# MIDI_Input.net
KiCad netlist of a schematic drawn in EAGLE
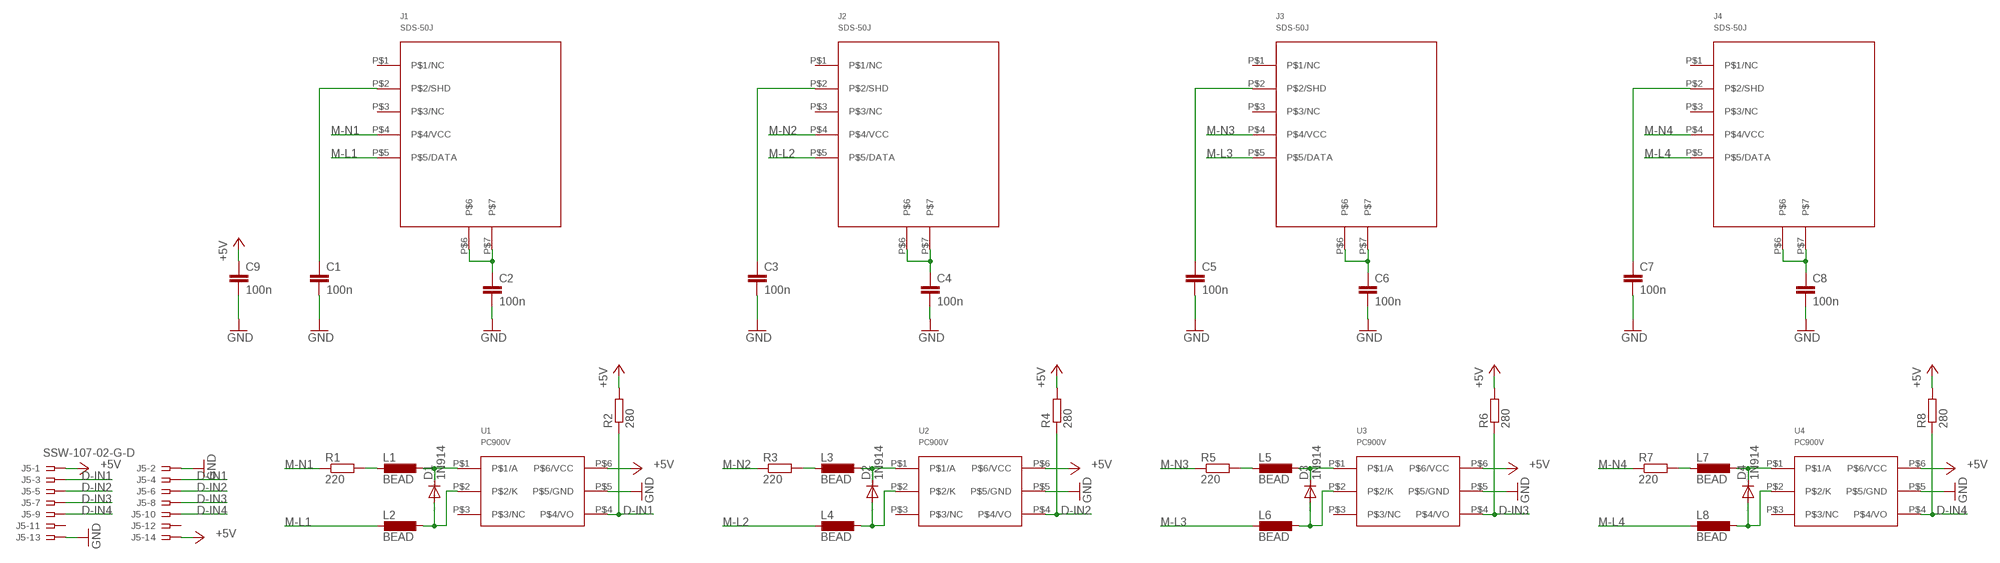
[diagram p0: schematic, sheet 1]

(export (version "E")
  (design (tool "Eeschema 10.0.6"))
  (components
    (comp (ref "C1")
      (value "100n")
      (footprint "eagle-import:C0805")
      (libsource (lib "eagle-import") (part "C-EUC0805"))
    )
    (comp (ref "C2")
      (value "100n")
      (footprint "eagle-import:C0805")
      (libsource (lib "eagle-import") (part "C-EUC0805"))
    )
    (comp (ref "C3")
      (value "100n")
      (footprint "eagle-import:C0805")
      (libsource (lib "eagle-import") (part "C-EUC0805"))
    )
    (comp (ref "C4")
      (value "100n")
      (footprint "eagle-import:C0805")
      (libsource (lib "eagle-import") (part "C-EUC0805"))
    )
    (comp (ref "C5")
      (value "100n")
      (footprint "eagle-import:C0805")
      (libsource (lib "eagle-import") (part "C-EUC0805"))
    )
    (comp (ref "C6")
      (value "100n")
      (footprint "eagle-import:C0805")
      (libsource (lib "eagle-import") (part "C-EUC0805"))
    )
    (comp (ref "C7")
      (value "100n")
      (footprint "eagle-import:C0805")
      (libsource (lib "eagle-import") (part "C-EUC0805"))
    )
    (comp (ref "C8")
      (value "100n")
      (footprint "eagle-import:C0805")
      (libsource (lib "eagle-import") (part "C-EUC0805"))
    )
    (comp (ref "C9")
      (value "100n")
      (footprint "eagle-import:C0805")
      (libsource (lib "eagle-import") (part "C-EUC0805"))
    )
    (comp (ref "D1")
      (value "1N914")
      (footprint "eagle-import:SOD323-W")
      (libsource (lib "eagle-import") (part "1N914"))
    )
    (comp (ref "D2")
      (value "1N914")
      (footprint "eagle-import:SOD323-W")
      (libsource (lib "eagle-import") (part "1N914"))
    )
    (comp (ref "D3")
      (value "1N914")
      (footprint "eagle-import:SOD323-W")
      (libsource (lib "eagle-import") (part "1N914"))
    )
    (comp (ref "D4")
      (value "1N914")
      (footprint "eagle-import:SOD323-W")
      (libsource (lib "eagle-import") (part "1N914"))
    )
    (comp (ref "J1")
      (value "SDS-50J")
      (footprint "eagle-import:SDS-50J")
      (libsource (lib "eagle-import") (part "SDS-50J"))
    )
    (comp (ref "J2")
      (value "SDS-50J")
      (footprint "eagle-import:SDS-50J")
      (libsource (lib "eagle-import") (part "SDS-50J"))
    )
    (comp (ref "J3")
      (value "SDS-50J")
      (footprint "eagle-import:SDS-50J")
      (libsource (lib "eagle-import") (part "SDS-50J"))
    )
    (comp (ref "J4")
      (value "SDS-50J")
      (footprint "eagle-import:SDS-50J")
      (libsource (lib "eagle-import") (part "SDS-50J"))
    )
    (comp (ref "J5")
      (value "SSW-107-02-G-D")
      (footprint "eagle-import:SSW-107-02-G-D")
      (fields (field (name "MF") "Samtec Inc."))
      (libsource (lib "eagle-import") (part "SSW-107-02-G-D"))
    )
    (comp (ref "L1")
      (value "BEAD")
      (footprint "eagle-import:L0805")
      (libsource (lib "eagle-import") (part "BEAD"))
    )
    (comp (ref "L2")
      (value "BEAD")
      (footprint "eagle-import:L0805")
      (libsource (lib "eagle-import") (part "BEAD"))
    )
    (comp (ref "L3")
      (value "BEAD")
      (footprint "eagle-import:L0805")
      (libsource (lib "eagle-import") (part "BEAD"))
    )
    (comp (ref "L4")
      (value "BEAD")
      (footprint "eagle-import:L0805")
      (libsource (lib "eagle-import") (part "BEAD"))
    )
    (comp (ref "L5")
      (value "BEAD")
      (footprint "eagle-import:L0805")
      (libsource (lib "eagle-import") (part "BEAD"))
    )
    (comp (ref "L6")
      (value "BEAD")
      (footprint "eagle-import:L0805")
      (libsource (lib "eagle-import") (part "BEAD"))
    )
    (comp (ref "L7")
      (value "BEAD")
      (footprint "eagle-import:L0805")
      (libsource (lib "eagle-import") (part "BEAD"))
    )
    (comp (ref "L8")
      (value "BEAD")
      (footprint "eagle-import:L0805")
      (libsource (lib "eagle-import") (part "BEAD"))
    )
    (comp (ref "R1")
      (value "220")
      (footprint "eagle-import:R0805")
      (libsource (lib "eagle-import") (part "R-EU_R0805"))
    )
    (comp (ref "R2")
      (value "280")
      (footprint "eagle-import:R0805")
      (libsource (lib "eagle-import") (part "R-EU_R0805"))
    )
    (comp (ref "R3")
      (value "220")
      (footprint "eagle-import:R0805")
      (libsource (lib "eagle-import") (part "R-EU_R0805"))
    )
    (comp (ref "R4")
      (value "280")
      (footprint "eagle-import:R0805")
      (libsource (lib "eagle-import") (part "R-EU_R0805"))
    )
    (comp (ref "R5")
      (value "220")
      (footprint "eagle-import:R0805")
      (libsource (lib "eagle-import") (part "R-EU_R0805"))
    )
    (comp (ref "R6")
      (value "280")
      (footprint "eagle-import:R0805")
      (libsource (lib "eagle-import") (part "R-EU_R0805"))
    )
    (comp (ref "R7")
      (value "220")
      (footprint "eagle-import:R0805")
      (libsource (lib "eagle-import") (part "R-EU_R0805"))
    )
    (comp (ref "R8")
      (value "280")
      (footprint "eagle-import:R0805")
      (libsource (lib "eagle-import") (part "R-EU_R0805"))
    )
    (comp (ref "U1")
      (value "PC900V")
      (footprint "eagle-import:DIL06")
      (libsource (lib "eagle-import") (part "PC900V"))
    )
    (comp (ref "U2")
      (value "PC900V")
      (footprint "eagle-import:DIL06")
      (libsource (lib "eagle-import") (part "PC900V"))
    )
    (comp (ref "U3")
      (value "PC900V")
      (footprint "eagle-import:DIL06")
      (libsource (lib "eagle-import") (part "PC900V"))
    )
    (comp (ref "U4")
      (value "PC900V")
      (footprint "eagle-import:DIL06")
      (libsource (lib "eagle-import") (part "PC900V"))
    )
  )
  (nets
    (net (code "1") (name "+5V") (class "Default")
      (node (ref "C9") (pin "1") (pinfunction "1_1") (pintype "passive"))
      (node (ref "J5") (pin "1") (pinfunction "1_1") (pintype "passive"))
      (node (ref "J5") (pin "14") (pinfunction "1_14") (pintype "passive"))
      (node (ref "R2") (pin "2") (pinfunction "2_2") (pintype "passive"))
      (node (ref "R4") (pin "2") (pinfunction "2_2") (pintype "passive"))
      (node (ref "R6") (pin "2") (pinfunction "2_2") (pintype "passive"))
      (node (ref "R8") (pin "2") (pinfunction "2_2") (pintype "passive"))
      (node (ref "U1") (pin "P$6") (pinfunction "P$6/VCC_P$6") (pintype "bidirectional"))
      (node (ref "U2") (pin "P$6") (pinfunction "P$6/VCC_P$6") (pintype "bidirectional"))
      (node (ref "U3") (pin "P$6") (pinfunction "P$6/VCC_P$6") (pintype "bidirectional"))
      (node (ref "U4") (pin "P$6") (pinfunction "P$6/VCC_P$6") (pintype "bidirectional"))
    )
    (net (code "2") (name "/D-IN1") (class "Default")
      (node (ref "J5") (pin "3") (pinfunction "1_3") (pintype "passive"))
      (node (ref "J5") (pin "4") (pinfunction "1_4") (pintype "passive"))
      (node (ref "R2") (pin "1") (pinfunction "1_1") (pintype "passive"))
      (node (ref "U1") (pin "P$4") (pinfunction "P$4/VO_P$4") (pintype "bidirectional"))
    )
    (net (code "3") (name "/D-IN2") (class "Default")
      (node (ref "J5") (pin "5") (pinfunction "1_5") (pintype "passive"))
      (node (ref "J5") (pin "6") (pinfunction "1_6") (pintype "passive"))
      (node (ref "R4") (pin "1") (pinfunction "1_1") (pintype "passive"))
      (node (ref "U2") (pin "P$4") (pinfunction "P$4/VO_P$4") (pintype "bidirectional"))
    )
    (net (code "4") (name "/D-IN3") (class "Default")
      (node (ref "J5") (pin "7") (pinfunction "1_7") (pintype "passive"))
      (node (ref "J5") (pin "8") (pinfunction "1_8") (pintype "passive"))
      (node (ref "R6") (pin "1") (pinfunction "1_1") (pintype "passive"))
      (node (ref "U3") (pin "P$4") (pinfunction "P$4/VO_P$4") (pintype "bidirectional"))
    )
    (net (code "5") (name "/D-IN4") (class "Default")
      (node (ref "J5") (pin "10") (pinfunction "1_10") (pintype "passive"))
      (node (ref "J5") (pin "9") (pinfunction "1_9") (pintype "passive"))
      (node (ref "R8") (pin "1") (pinfunction "1_1") (pintype "passive"))
      (node (ref "U4") (pin "P$4") (pinfunction "P$4/VO_P$4") (pintype "bidirectional"))
    )
    (net (code "6") (name "/M-L1") (class "Default")
      (node (ref "J1") (pin "P$5") (pinfunction "P$5/DATA_P$5") (pintype "bidirectional"))
      (node (ref "L2") (pin "1") (pinfunction "1_1") (pintype "passive"))
    )
    (net (code "7") (name "/M-L2") (class "Default")
      (node (ref "J2") (pin "P$5") (pinfunction "P$5/DATA_P$5") (pintype "bidirectional"))
      (node (ref "L4") (pin "1") (pinfunction "1_1") (pintype "passive"))
    )
    (net (code "8") (name "/M-L3") (class "Default")
      (node (ref "J3") (pin "P$5") (pinfunction "P$5/DATA_P$5") (pintype "bidirectional"))
      (node (ref "L6") (pin "1") (pinfunction "1_1") (pintype "passive"))
    )
    (net (code "9") (name "/M-L4") (class "Default")
      (node (ref "J4") (pin "P$5") (pinfunction "P$5/DATA_P$5") (pintype "bidirectional"))
      (node (ref "L8") (pin "1") (pinfunction "1_1") (pintype "passive"))
    )
    (net (code "10") (name "/M-N1") (class "Default")
      (node (ref "J1") (pin "P$4") (pinfunction "P$4/VCC_P$4") (pintype "bidirectional"))
      (node (ref "R1") (pin "1") (pinfunction "1_1") (pintype "passive"))
    )
    (net (code "11") (name "/M-N2") (class "Default")
      (node (ref "J2") (pin "P$4") (pinfunction "P$4/VCC_P$4") (pintype "bidirectional"))
      (node (ref "R3") (pin "1") (pinfunction "1_1") (pintype "passive"))
    )
    (net (code "12") (name "/M-N3") (class "Default")
      (node (ref "J3") (pin "P$4") (pinfunction "P$4/VCC_P$4") (pintype "bidirectional"))
      (node (ref "R5") (pin "1") (pinfunction "1_1") (pintype "passive"))
    )
    (net (code "13") (name "/M-N4") (class "Default")
      (node (ref "J4") (pin "P$4") (pinfunction "P$4/VCC_P$4") (pintype "bidirectional"))
      (node (ref "R7") (pin "1") (pinfunction "1_1") (pintype "passive"))
    )
    (net (code "14") (name "GND") (class "Default")
      (node (ref "C1") (pin "2") (pinfunction "2_2") (pintype "passive"))
      (node (ref "C2") (pin "2") (pinfunction "2_2") (pintype "passive"))
      (node (ref "C3") (pin "2") (pinfunction "2_2") (pintype "passive"))
      (node (ref "C4") (pin "2") (pinfunction "2_2") (pintype "passive"))
      (node (ref "C5") (pin "2") (pinfunction "2_2") (pintype "passive"))
      (node (ref "C6") (pin "2") (pinfunction "2_2") (pintype "passive"))
      (node (ref "C7") (pin "2") (pinfunction "2_2") (pintype "passive"))
      (node (ref "C8") (pin "2") (pinfunction "2_2") (pintype "passive"))
      (node (ref "C9") (pin "2") (pinfunction "2_2") (pintype "passive"))
      (node (ref "J5") (pin "13") (pinfunction "1_13") (pintype "passive"))
      (node (ref "J5") (pin "2") (pinfunction "1_2") (pintype "passive"))
      (node (ref "U1") (pin "P$5") (pinfunction "P$5/GND_P$5") (pintype "bidirectional"))
      (node (ref "U2") (pin "P$5") (pinfunction "P$5/GND_P$5") (pintype "bidirectional"))
      (node (ref "U3") (pin "P$5") (pinfunction "P$5/GND_P$5") (pintype "bidirectional"))
      (node (ref "U4") (pin "P$5") (pinfunction "P$5/GND_P$5") (pintype "bidirectional"))
    )
    (net (code "15") (name "Net-(C2-Pad1)") (class "Default")
      (node (ref "C2") (pin "1") (pinfunction "1_1") (pintype "passive"))
      (node (ref "J1") (pin "P$6") (pinfunction "P$6_P$6") (pintype "bidirectional"))
      (node (ref "J1") (pin "P$7") (pinfunction "P$7_P$7") (pintype "bidirectional"))
    )
    (net (code "16") (name "Net-(C4-Pad1)") (class "Default")
      (node (ref "C4") (pin "1") (pinfunction "1_1") (pintype "passive"))
      (node (ref "J2") (pin "P$6") (pinfunction "P$6_P$6") (pintype "bidirectional"))
      (node (ref "J2") (pin "P$7") (pinfunction "P$7_P$7") (pintype "bidirectional"))
    )
    (net (code "17") (name "Net-(C6-Pad1)") (class "Default")
      (node (ref "C6") (pin "1") (pinfunction "1_1") (pintype "passive"))
      (node (ref "J3") (pin "P$6") (pinfunction "P$6_P$6") (pintype "bidirectional"))
      (node (ref "J3") (pin "P$7") (pinfunction "P$7_P$7") (pintype "bidirectional"))
    )
    (net (code "18") (name "Net-(C8-Pad1)") (class "Default")
      (node (ref "C8") (pin "1") (pinfunction "1_1") (pintype "passive"))
      (node (ref "J4") (pin "P$6") (pinfunction "P$6_P$6") (pintype "bidirectional"))
      (node (ref "J4") (pin "P$7") (pinfunction "P$7_P$7") (pintype "bidirectional"))
    )
    (net (code "19") (name "Net-(J1-P$2{slash}SHD)") (class "Default")
      (node (ref "C1") (pin "1") (pinfunction "1_1") (pintype "passive"))
      (node (ref "J1") (pin "P$2") (pinfunction "P$2/SHD_P$2") (pintype "bidirectional"))
    )
    (net (code "20") (name "Net-(J2-P$2{slash}SHD)") (class "Default")
      (node (ref "C3") (pin "1") (pinfunction "1_1") (pintype "passive"))
      (node (ref "J2") (pin "P$2") (pinfunction "P$2/SHD_P$2") (pintype "bidirectional"))
    )
    (net (code "21") (name "Net-(J3-P$2{slash}SHD)") (class "Default")
      (node (ref "C5") (pin "1") (pinfunction "1_1") (pintype "passive"))
      (node (ref "J3") (pin "P$2") (pinfunction "P$2/SHD_P$2") (pintype "bidirectional"))
    )
    (net (code "22") (name "Net-(J4-P$2{slash}SHD)") (class "Default")
      (node (ref "C7") (pin "1") (pinfunction "1_1") (pintype "passive"))
      (node (ref "J4") (pin "P$2") (pinfunction "P$2/SHD_P$2") (pintype "bidirectional"))
    )
    (net (code "23") (name "Net-(L1-Pad1)") (class "Default")
      (node (ref "L1") (pin "1") (pinfunction "1_1") (pintype "passive"))
      (node (ref "R1") (pin "2") (pinfunction "2_2") (pintype "passive"))
    )
    (net (code "24") (name "Net-(L3-Pad1)") (class "Default")
      (node (ref "L3") (pin "1") (pinfunction "1_1") (pintype "passive"))
      (node (ref "R3") (pin "2") (pinfunction "2_2") (pintype "passive"))
    )
    (net (code "25") (name "Net-(L5-Pad1)") (class "Default")
      (node (ref "L5") (pin "1") (pinfunction "1_1") (pintype "passive"))
      (node (ref "R5") (pin "2") (pinfunction "2_2") (pintype "passive"))
    )
    (net (code "26") (name "Net-(L7-Pad1)") (class "Default")
      (node (ref "L7") (pin "1") (pinfunction "1_1") (pintype "passive"))
      (node (ref "R7") (pin "2") (pinfunction "2_2") (pintype "passive"))
    )
    (net (code "27") (name "Net-(U1-P$1{slash}A)") (class "Default")
      (node (ref "D1") (pin "C") (pinfunction "C_C") (pintype "passive"))
      (node (ref "L1") (pin "2") (pinfunction "2_2") (pintype "passive"))
      (node (ref "U1") (pin "P$1") (pinfunction "P$1/A_P$1") (pintype "bidirectional"))
    )
    (net (code "28") (name "Net-(U1-P$2{slash}K)") (class "Default")
      (node (ref "D1") (pin "A") (pinfunction "A_A") (pintype "passive"))
      (node (ref "L2") (pin "2") (pinfunction "2_2") (pintype "passive"))
      (node (ref "U1") (pin "P$2") (pinfunction "P$2/K_P$2") (pintype "bidirectional"))
    )
    (net (code "29") (name "Net-(U2-P$1{slash}A)") (class "Default")
      (node (ref "D2") (pin "C") (pinfunction "C_C") (pintype "passive"))
      (node (ref "L3") (pin "2") (pinfunction "2_2") (pintype "passive"))
      (node (ref "U2") (pin "P$1") (pinfunction "P$1/A_P$1") (pintype "bidirectional"))
    )
    (net (code "30") (name "Net-(U2-P$2{slash}K)") (class "Default")
      (node (ref "D2") (pin "A") (pinfunction "A_A") (pintype "passive"))
      (node (ref "L4") (pin "2") (pinfunction "2_2") (pintype "passive"))
      (node (ref "U2") (pin "P$2") (pinfunction "P$2/K_P$2") (pintype "bidirectional"))
    )
    (net (code "31") (name "Net-(U3-P$1{slash}A)") (class "Default")
      (node (ref "D3") (pin "C") (pinfunction "C_C") (pintype "passive"))
      (node (ref "L5") (pin "2") (pinfunction "2_2") (pintype "passive"))
      (node (ref "U3") (pin "P$1") (pinfunction "P$1/A_P$1") (pintype "bidirectional"))
    )
    (net (code "32") (name "Net-(U3-P$2{slash}K)") (class "Default")
      (node (ref "D3") (pin "A") (pinfunction "A_A") (pintype "passive"))
      (node (ref "L6") (pin "2") (pinfunction "2_2") (pintype "passive"))
      (node (ref "U3") (pin "P$2") (pinfunction "P$2/K_P$2") (pintype "bidirectional"))
    )
    (net (code "33") (name "Net-(U4-P$1{slash}A)") (class "Default")
      (node (ref "D4") (pin "C") (pinfunction "C_C") (pintype "passive"))
      (node (ref "L7") (pin "2") (pinfunction "2_2") (pintype "passive"))
      (node (ref "U4") (pin "P$1") (pinfunction "P$1/A_P$1") (pintype "bidirectional"))
    )
    (net (code "34") (name "Net-(U4-P$2{slash}K)") (class "Default")
      (node (ref "D4") (pin "A") (pinfunction "A_A") (pintype "passive"))
      (node (ref "L8") (pin "2") (pinfunction "2_2") (pintype "passive"))
      (node (ref "U4") (pin "P$2") (pinfunction "P$2/K_P$2") (pintype "bidirectional"))
    )
    (net (code "35") (name "unconnected-(J1-P$1{slash}NC-PadP$1)") (class "Default")
      (node (ref "J1") (pin "P$1") (pinfunction "P$1/NC_P$1") (pintype "bidirectional"))
    )
    (net (code "36") (name "unconnected-(J1-P$3{slash}NC-PadP$3)") (class "Default")
      (node (ref "J1") (pin "P$3") (pinfunction "P$3/NC_P$3") (pintype "bidirectional"))
    )
    (net (code "37") (name "unconnected-(J2-P$1{slash}NC-PadP$1)") (class "Default")
      (node (ref "J2") (pin "P$1") (pinfunction "P$1/NC_P$1") (pintype "bidirectional"))
    )
    (net (code "38") (name "unconnected-(J2-P$3{slash}NC-PadP$3)") (class "Default")
      (node (ref "J2") (pin "P$3") (pinfunction "P$3/NC_P$3") (pintype "bidirectional"))
    )
    (net (code "39") (name "unconnected-(J3-P$1{slash}NC-PadP$1)") (class "Default")
      (node (ref "J3") (pin "P$1") (pinfunction "P$1/NC_P$1") (pintype "bidirectional"))
    )
    (net (code "40") (name "unconnected-(J3-P$3{slash}NC-PadP$3)") (class "Default")
      (node (ref "J3") (pin "P$3") (pinfunction "P$3/NC_P$3") (pintype "bidirectional"))
    )
    (net (code "41") (name "unconnected-(J4-P$1{slash}NC-PadP$1)") (class "Default")
      (node (ref "J4") (pin "P$1") (pinfunction "P$1/NC_P$1") (pintype "bidirectional"))
    )
    (net (code "42") (name "unconnected-(J4-P$3{slash}NC-PadP$3)") (class "Default")
      (node (ref "J4") (pin "P$3") (pinfunction "P$3/NC_P$3") (pintype "bidirectional"))
    )
    (net (code "43") (name "unconnected-(J5C-1-Pad11)") (class "Default")
      (node (ref "J5") (pin "11") (pinfunction "1_11") (pintype "passive"))
    )
    (net (code "44") (name "unconnected-(J5D-1-Pad12)") (class "Default")
      (node (ref "J5") (pin "12") (pinfunction "1_12") (pintype "passive"))
    )
    (net (code "45") (name "unconnected-(U1-P$3{slash}NC-PadP$3)") (class "Default")
      (node (ref "U1") (pin "P$3") (pinfunction "P$3/NC_P$3") (pintype "bidirectional"))
    )
    (net (code "46") (name "unconnected-(U2-P$3{slash}NC-PadP$3)") (class "Default")
      (node (ref "U2") (pin "P$3") (pinfunction "P$3/NC_P$3") (pintype "bidirectional"))
    )
    (net (code "47") (name "unconnected-(U3-P$3{slash}NC-PadP$3)") (class "Default")
      (node (ref "U3") (pin "P$3") (pinfunction "P$3/NC_P$3") (pintype "bidirectional"))
    )
    (net (code "48") (name "unconnected-(U4-P$3{slash}NC-PadP$3)") (class "Default")
      (node (ref "U4") (pin "P$3") (pinfunction "P$3/NC_P$3") (pintype "bidirectional"))
    )
  )
)
